# power.net
KiCad netlist of a schematic drawn in Altium Designer
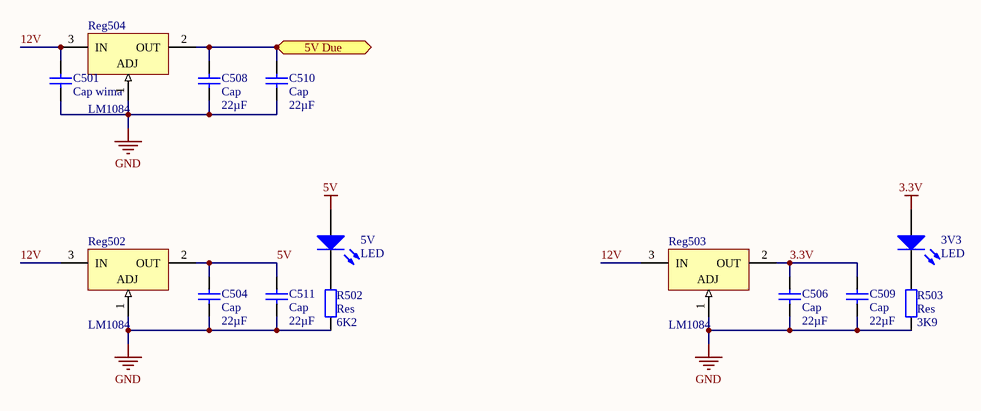
[diagram p0: power.SchDoc]

(export (version "E")
  (design (tool "Eeschema 10.0.6"))
  (components
    (comp (ref "3V3") (value "LED") (footprint "LED 3mm") (libsource (lib "ArduinoNano") (part "LED")))
    (comp (ref "5V") (value "LED") (footprint "LED 3mm") (libsource (lib "ArduinoNano") (part "LED")))
    (comp (ref "C501")
      (value "Cap wima")
      (footprint "Wima 11x16x7.2mm")
      (libsource (lib "ArduinoNano") (part "Cap wima"))
    )
    (comp (ref "C504")
      (value "Cap")
      (footprint "1206 footprint")
      (fields (field (name "ALTIUM_VALUE") "22µF"))
      (libsource (lib "ArduinoNano") (part "Cap"))
    )
    (comp (ref "C506")
      (value "Cap")
      (footprint "1206 footprint")
      (fields (field (name "ALTIUM_VALUE") "22µF"))
      (libsource (lib "ArduinoNano") (part "Cap"))
    )
    (comp (ref "C508")
      (value "Cap")
      (footprint "1206 footprint")
      (fields (field (name "ALTIUM_VALUE") "22µF"))
      (libsource (lib "ArduinoNano") (part "Cap"))
    )
    (comp (ref "C509")
      (value "Cap")
      (footprint "1206 footprint")
      (fields (field (name "ALTIUM_VALUE") "22µF"))
      (libsource (lib "ArduinoNano") (part "Cap"))
    )
    (comp (ref "C510")
      (value "Cap")
      (footprint "1206 footprint")
      (fields (field (name "ALTIUM_VALUE") "22µF"))
      (libsource (lib "ArduinoNano") (part "Cap"))
    )
    (comp (ref "C511")
      (value "Cap")
      (footprint "1206 footprint")
      (fields (field (name "ALTIUM_VALUE") "22µF"))
      (libsource (lib "ArduinoNano") (part "Cap"))
    )
    (comp (ref "R502")
      (value "Res")
      (footprint "1206 footprint")
      (fields (field (name "ALTIUM_VALUE") "6K2"))
      (libsource (lib "ArduinoNano") (part "Res"))
    )
    (comp (ref "R503")
      (value "Res")
      (footprint "1206 footprint")
      (fields (field (name "ALTIUM_VALUE") "3K9"))
      (libsource (lib "ArduinoNano") (part "Res"))
    )
    (comp (ref "Reg502")
      (value "LM1084")
      (footprint "LM1084")
      (libsource (lib "ArduinoNano") (part "LM1084"))
    )
    (comp (ref "Reg503")
      (value "LM1084")
      (footprint "LM1084")
      (libsource (lib "ArduinoNano") (part "LM1084"))
    )
    (comp (ref "Reg504")
      (value "LM1084")
      (footprint "LM1084")
      (libsource (lib "ArduinoNano") (part "LM1084"))
    )
  )
  (nets
    (net (code "1") (name "/5V Due") (class "Default")
      (node (ref "C508") (pin "2") (pinfunction "2_2") (pintype "passive"))
      (node (ref "C510") (pin "2") (pinfunction "2_2") (pintype "passive"))
      (node (ref "Reg504") (pin "2") (pinfunction "OUT_2") (pintype "power_in"))
    )
    (net (code "2") (name "/12V") (class "Default")
      (node (ref "C501") (pin "2") (pinfunction "2_2") (pintype "passive"))
      (node (ref "Reg502") (pin "3") (pinfunction "IN_3") (pintype "power_in"))
      (node (ref "Reg503") (pin "3") (pinfunction "IN_3") (pintype "power_in"))
      (node (ref "Reg504") (pin "3") (pinfunction "IN_3") (pintype "power_in"))
    )
    (net (code "3") (name "3.3V") (class "Default")
      (node (ref "3V3") (pin "1") (pinfunction "A_1") (pintype "passive"))
      (node (ref "C506") (pin "2") (pinfunction "2_2") (pintype "passive"))
      (node (ref "C509") (pin "2") (pinfunction "2_2") (pintype "passive"))
      (node (ref "Reg503") (pin "2") (pinfunction "OUT_2") (pintype "power_in"))
    )
    (net (code "4") (name "5V") (class "Default")
      (node (ref "5V") (pin "1") (pinfunction "A_1") (pintype "passive"))
      (node (ref "C504") (pin "2") (pinfunction "2_2") (pintype "passive"))
      (node (ref "C511") (pin "2") (pinfunction "2_2") (pintype "passive"))
      (node (ref "Reg502") (pin "2") (pinfunction "OUT_2") (pintype "power_in"))
    )
    (net (code "5") (name "GND") (class "Default")
      (node (ref "C501") (pin "1") (pinfunction "1_1") (pintype "passive"))
      (node (ref "C504") (pin "1") (pinfunction "1_1") (pintype "passive"))
      (node (ref "C506") (pin "1") (pinfunction "1_1") (pintype "passive"))
      (node (ref "C508") (pin "1") (pinfunction "1_1") (pintype "passive"))
      (node (ref "C509") (pin "1") (pinfunction "1_1") (pintype "passive"))
      (node (ref "C510") (pin "1") (pinfunction "1_1") (pintype "passive"))
      (node (ref "C511") (pin "1") (pinfunction "1_1") (pintype "passive"))
      (node (ref "R502") (pin "1") (pinfunction "1_1") (pintype "passive"))
      (node (ref "R503") (pin "1") (pinfunction "1_1") (pintype "passive"))
      (node (ref "Reg502") (pin "1") (pinfunction "ADJ_1") (pintype "input"))
      (node (ref "Reg503") (pin "1") (pinfunction "ADJ_1") (pintype "input"))
      (node (ref "Reg504") (pin "1") (pinfunction "ADJ_1") (pintype "input"))
    )
    (net (code "6") (name "Net-(3V3-K)") (class "Default")
      (node (ref "3V3") (pin "2") (pinfunction "K_2") (pintype "passive"))
      (node (ref "R503") (pin "2") (pinfunction "2_2") (pintype "passive"))
    )
    (net (code "7") (name "Net-(5V-K)") (class "Default")
      (node (ref "5V") (pin "2") (pinfunction "K_2") (pintype "passive"))
      (node (ref "R502") (pin "2") (pinfunction "2_2") (pintype "passive"))
    )
  )
)
